# Core.net
KiCad netlist of a schematic drawn in Altium Designer
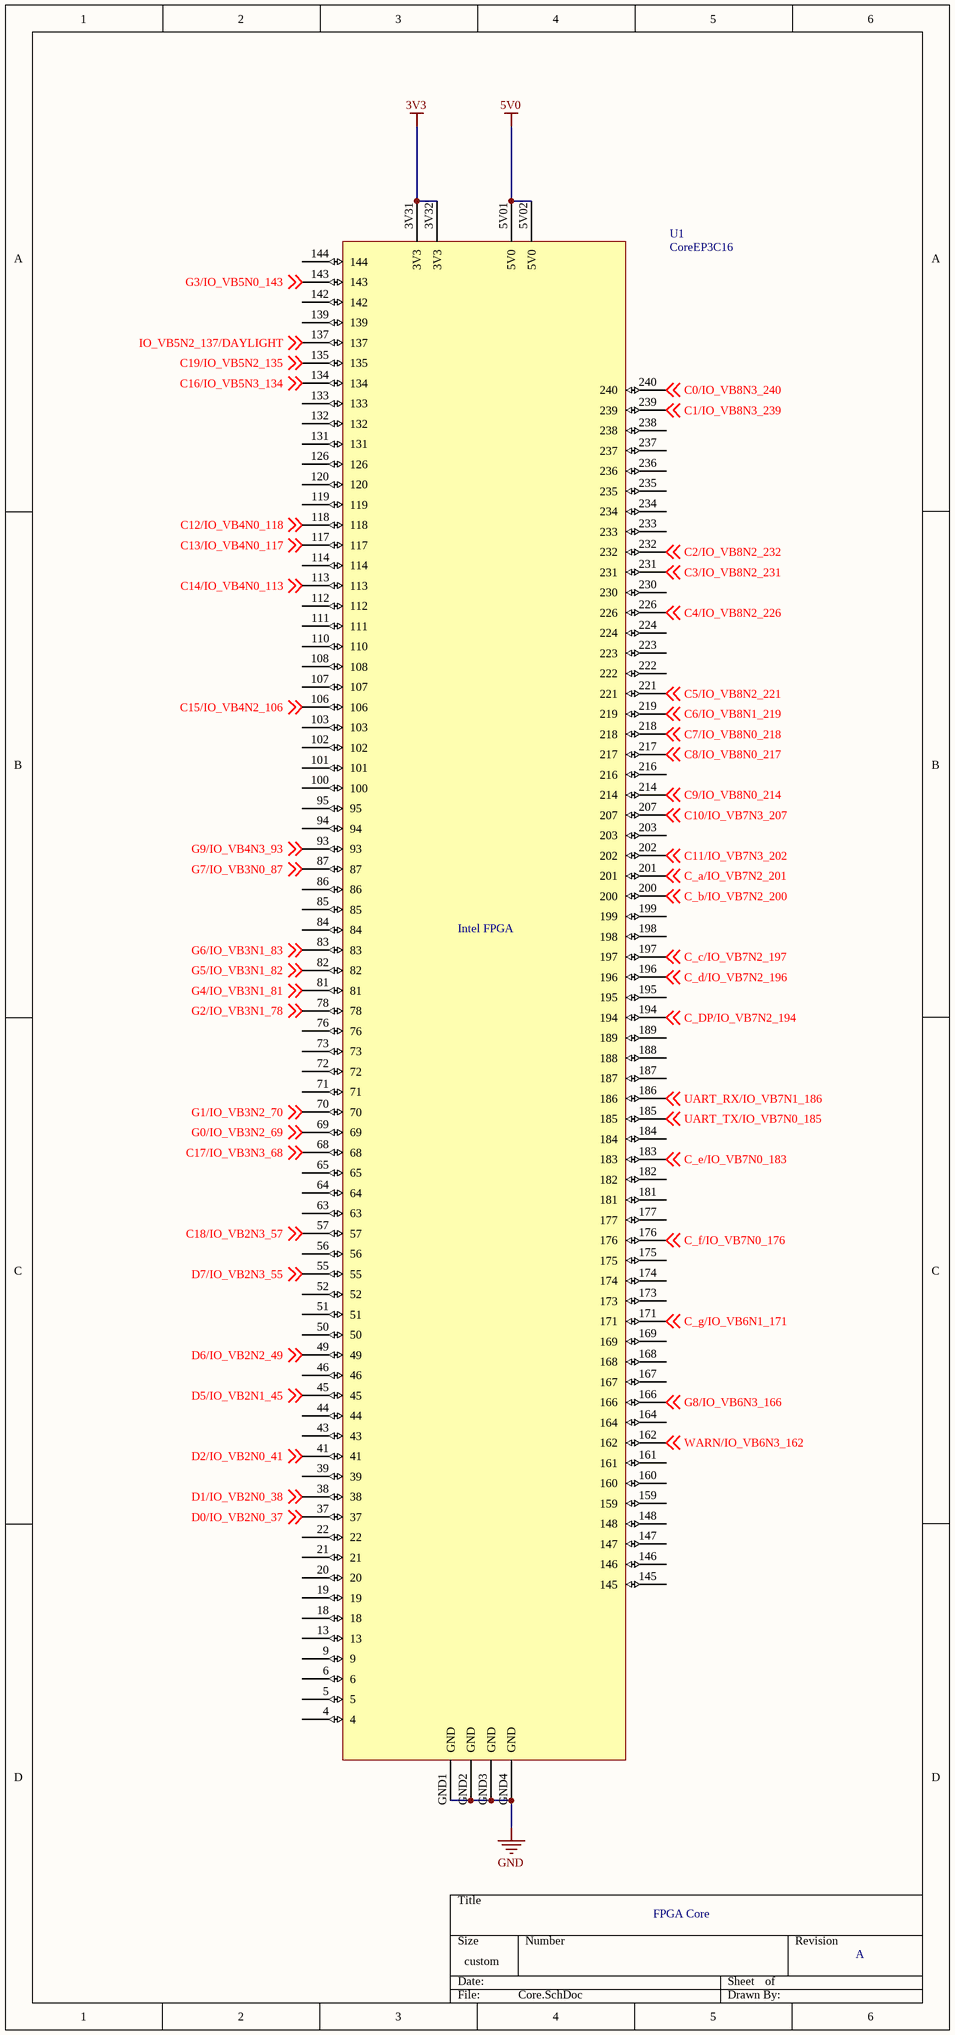
[diagram p0: Core.SchDoc]

(export (version "E")
  (design (tool "Eeschema 10.0.6"))
  (components
    (comp (ref "U1")
      (value "CoreEP3C16")
      (footprint "COREEP3C16")
      (description "Intel FPGA Core")
      (libsource (lib "schematics") (part "CoreEP3C16"))
    )
  )
  (nets
    (net (code "1") (name "3V3") (class "Default")
      (node (ref "U1") (pin "3V31") (pinfunction "3V3_3V31") (pintype "power_in"))
      (node (ref "U1") (pin "3V32") (pinfunction "3V3_3V32") (pintype "power_in"))
    )
    (net (code "2") (name "5V0") (class "Default")
      (node (ref "U1") (pin "5V01") (pinfunction "5V0_5V01") (pintype "power_in"))
      (node (ref "U1") (pin "5V02") (pinfunction "5V0_5V02") (pintype "power_in"))
    )
    (net (code "3") (name "C0{slash}IO_VB8N3_240") (class "Default")
      (node (ref "U1") (pin "240") (pinfunction "240_240") (pintype "bidirectional"))
    )
    (net (code "4") (name "C1{slash}IO_VB8N3_239") (class "Default")
      (node (ref "U1") (pin "239") (pinfunction "239_239") (pintype "bidirectional"))
    )
    (net (code "5") (name "C2{slash}IO_VB8N2_232") (class "Default")
      (node (ref "U1") (pin "232") (pinfunction "232_232") (pintype "bidirectional"))
    )
    (net (code "6") (name "C3{slash}IO_VB8N2_231") (class "Default")
      (node (ref "U1") (pin "231") (pinfunction "231_231") (pintype "bidirectional"))
    )
    (net (code "7") (name "C4{slash}IO_VB8N2_226") (class "Default")
      (node (ref "U1") (pin "226") (pinfunction "226_226") (pintype "bidirectional"))
    )
    (net (code "8") (name "C5{slash}IO_VB8N2_221") (class "Default")
      (node (ref "U1") (pin "221") (pinfunction "221_221") (pintype "bidirectional"))
    )
    (net (code "9") (name "C6{slash}IO_VB8N1_219") (class "Default")
      (node (ref "U1") (pin "219") (pinfunction "219_219") (pintype "bidirectional"))
    )
    (net (code "10") (name "C7{slash}IO_VB8N0_218") (class "Default")
      (node (ref "U1") (pin "218") (pinfunction "218_218") (pintype "bidirectional"))
    )
    (net (code "11") (name "C8{slash}IO_VB8N0_217") (class "Default")
      (node (ref "U1") (pin "217") (pinfunction "217_217") (pintype "bidirectional"))
    )
    (net (code "12") (name "C9{slash}IO_VB8N0_214") (class "Default")
      (node (ref "U1") (pin "214") (pinfunction "214_214") (pintype "bidirectional"))
    )
    (net (code "13") (name "C10{slash}IO_VB7N3_207") (class "Default")
      (node (ref "U1") (pin "207") (pinfunction "207_207") (pintype "bidirectional"))
    )
    (net (code "14") (name "C11{slash}IO_VB7N3_202") (class "Default")
      (node (ref "U1") (pin "202") (pinfunction "202_202") (pintype "bidirectional"))
    )
    (net (code "15") (name "C12{slash}IO_VB4N0_118") (class "Default")
      (node (ref "U1") (pin "118") (pinfunction "118_118") (pintype "bidirectional"))
    )
    (net (code "16") (name "C13{slash}IO_VB4N0_117") (class "Default")
      (node (ref "U1") (pin "117") (pinfunction "117_117") (pintype "bidirectional"))
    )
    (net (code "17") (name "C14{slash}IO_VB4N0_113") (class "Default")
      (node (ref "U1") (pin "113") (pinfunction "113_113") (pintype "bidirectional"))
    )
    (net (code "18") (name "C15{slash}IO_VB4N2_106") (class "Default")
      (node (ref "U1") (pin "106") (pinfunction "106_106") (pintype "bidirectional"))
    )
    (net (code "19") (name "C16{slash}IO_VB5N3_134") (class "Default")
      (node (ref "U1") (pin "134") (pinfunction "134_134") (pintype "bidirectional"))
    )
    (net (code "20") (name "C17{slash}IO_VB3N3_68") (class "Default")
      (node (ref "U1") (pin "68") (pinfunction "68_68") (pintype "bidirectional"))
    )
    (net (code "21") (name "C18{slash}IO_VB2N3_57") (class "Default")
      (node (ref "U1") (pin "57") (pinfunction "57_57") (pintype "bidirectional"))
    )
    (net (code "22") (name "C19{slash}IO_VB5N2_135") (class "Default")
      (node (ref "U1") (pin "135") (pinfunction "135_135") (pintype "bidirectional"))
    )
    (net (code "23") (name "C_DP{slash}IO_VB7N2_194") (class "Default")
      (node (ref "U1") (pin "194") (pinfunction "194_194") (pintype "bidirectional"))
    )
    (net (code "24") (name "C_a{slash}IO_VB7N2_201") (class "Default")
      (node (ref "U1") (pin "201") (pinfunction "201_201") (pintype "bidirectional"))
    )
    (net (code "25") (name "C_b{slash}IO_VB7N2_200") (class "Default")
      (node (ref "U1") (pin "200") (pinfunction "200_200") (pintype "bidirectional"))
    )
    (net (code "26") (name "C_c{slash}IO_VB7N2_197") (class "Default")
      (node (ref "U1") (pin "197") (pinfunction "197_197") (pintype "bidirectional"))
    )
    (net (code "27") (name "C_d{slash}IO_VB7N2_196") (class "Default")
      (node (ref "U1") (pin "196") (pinfunction "196_196") (pintype "bidirectional"))
    )
    (net (code "28") (name "C_e{slash}IO_VB7N0_183") (class "Default")
      (node (ref "U1") (pin "183") (pinfunction "183_183") (pintype "bidirectional"))
    )
    (net (code "29") (name "C_f{slash}IO_VB7N0_176") (class "Default")
      (node (ref "U1") (pin "176") (pinfunction "176_176") (pintype "bidirectional"))
    )
    (net (code "30") (name "C_g{slash}IO_VB6N1_171") (class "Default")
      (node (ref "U1") (pin "171") (pinfunction "171_171") (pintype "bidirectional"))
    )
    (net (code "31") (name "D0{slash}IO_VB2N0_37") (class "Default")
      (node (ref "U1") (pin "37") (pinfunction "37_37") (pintype "bidirectional"))
    )
    (net (code "32") (name "D1{slash}IO_VB2N0_38") (class "Default")
      (node (ref "U1") (pin "38") (pinfunction "38_38") (pintype "bidirectional"))
    )
    (net (code "33") (name "D2{slash}IO_VB2N0_41") (class "Default")
      (node (ref "U1") (pin "41") (pinfunction "41_41") (pintype "bidirectional"))
    )
    (net (code "34") (name "D5{slash}IO_VB2N1_45") (class "Default")
      (node (ref "U1") (pin "45") (pinfunction "45_45") (pintype "bidirectional"))
    )
    (net (code "35") (name "D6{slash}IO_VB2N2_49") (class "Default")
      (node (ref "U1") (pin "49") (pinfunction "49_49") (pintype "bidirectional"))
    )
    (net (code "36") (name "D7{slash}IO_VB2N3_55") (class "Default")
      (node (ref "U1") (pin "55") (pinfunction "55_55") (pintype "bidirectional"))
    )
    (net (code "37") (name "G0{slash}IO_VB3N2_69") (class "Default")
      (node (ref "U1") (pin "69") (pinfunction "69_69") (pintype "bidirectional"))
    )
    (net (code "38") (name "G1{slash}IO_VB3N2_70") (class "Default")
      (node (ref "U1") (pin "70") (pinfunction "70_70") (pintype "bidirectional"))
    )
    (net (code "39") (name "G2{slash}IO_VB3N1_78") (class "Default")
      (node (ref "U1") (pin "78") (pinfunction "78_78") (pintype "bidirectional"))
    )
    (net (code "40") (name "G3{slash}IO_VB5N0_143") (class "Default")
      (node (ref "U1") (pin "143") (pinfunction "143_143") (pintype "bidirectional"))
    )
    (net (code "41") (name "G4{slash}IO_VB3N1_81") (class "Default")
      (node (ref "U1") (pin "81") (pinfunction "81_81") (pintype "bidirectional"))
    )
    (net (code "42") (name "G5{slash}IO_VB3N1_82") (class "Default")
      (node (ref "U1") (pin "82") (pinfunction "82_82") (pintype "bidirectional"))
    )
    (net (code "43") (name "G6{slash}IO_VB3N1_83") (class "Default")
      (node (ref "U1") (pin "83") (pinfunction "83_83") (pintype "bidirectional"))
    )
    (net (code "44") (name "G7{slash}IO_VB3N0_87") (class "Default")
      (node (ref "U1") (pin "87") (pinfunction "87_87") (pintype "bidirectional"))
    )
    (net (code "45") (name "G8{slash}IO_VB6N3_166") (class "Default")
      (node (ref "U1") (pin "166") (pinfunction "166_166") (pintype "bidirectional"))
    )
    (net (code "46") (name "G9{slash}IO_VB4N3_93") (class "Default")
      (node (ref "U1") (pin "93") (pinfunction "93_93") (pintype "bidirectional"))
    )
    (net (code "47") (name "GND") (class "Default")
      (node (ref "U1") (pin "GND1") (pinfunction "GND_GND1") (pintype "power_in"))
      (node (ref "U1") (pin "GND2") (pinfunction "GND_GND2") (pintype "power_in"))
      (node (ref "U1") (pin "GND3") (pinfunction "GND_GND3") (pintype "power_in"))
      (node (ref "U1") (pin "GND4") (pinfunction "GND_GND4") (pintype "power_in"))
    )
    (net (code "48") (name "IO_VB5N2_137{slash}DAYLIGHT") (class "Default")
      (node (ref "U1") (pin "137") (pinfunction "137_137") (pintype "bidirectional"))
    )
    (net (code "49") (name "UART_RX{slash}IO_VB7N1_186") (class "Default")
      (node (ref "U1") (pin "186") (pinfunction "186_186") (pintype "bidirectional"))
    )
    (net (code "50") (name "UART_TX{slash}IO_VB7N0_185") (class "Default")
      (node (ref "U1") (pin "185") (pinfunction "185_185") (pintype "bidirectional"))
    )
    (net (code "51") (name "WARN{slash}IO_VB6N3_162") (class "Default")
      (node (ref "U1") (pin "162") (pinfunction "162_162") (pintype "bidirectional"))
    )
    (net (code "52") (name "unconnected-(U1-Pad4)") (class "Default")
      (node (ref "U1") (pin "4") (pinfunction "4_4") (pintype "bidirectional"))
    )
    (net (code "53") (name "unconnected-(U1-Pad5)") (class "Default")
      (node (ref "U1") (pin "5") (pinfunction "5_5") (pintype "bidirectional"))
    )
    (net (code "54") (name "unconnected-(U1-Pad6)") (class "Default")
      (node (ref "U1") (pin "6") (pinfunction "6_6") (pintype "bidirectional"))
    )
    (net (code "55") (name "unconnected-(U1-Pad9)") (class "Default")
      (node (ref "U1") (pin "9") (pinfunction "9_9") (pintype "bidirectional"))
    )
    (net (code "56") (name "unconnected-(U1-Pad13)") (class "Default")
      (node (ref "U1") (pin "13") (pinfunction "13_13") (pintype "bidirectional"))
    )
    (net (code "57") (name "unconnected-(U1-Pad18)") (class "Default")
      (node (ref "U1") (pin "18") (pinfunction "18_18") (pintype "bidirectional"))
    )
    (net (code "58") (name "unconnected-(U1-Pad19)") (class "Default")
      (node (ref "U1") (pin "19") (pinfunction "19_19") (pintype "bidirectional"))
    )
    (net (code "59") (name "unconnected-(U1-Pad20)") (class "Default")
      (node (ref "U1") (pin "20") (pinfunction "20_20") (pintype "bidirectional"))
    )
    (net (code "60") (name "unconnected-(U1-Pad21)") (class "Default")
      (node (ref "U1") (pin "21") (pinfunction "21_21") (pintype "bidirectional"))
    )
    (net (code "61") (name "unconnected-(U1-Pad22)") (class "Default")
      (node (ref "U1") (pin "22") (pinfunction "22_22") (pintype "bidirectional"))
    )
    (net (code "62") (name "unconnected-(U1-Pad39)") (class "Default")
      (node (ref "U1") (pin "39") (pinfunction "39_39") (pintype "bidirectional"))
    )
    (net (code "63") (name "unconnected-(U1-Pad43)") (class "Default")
      (node (ref "U1") (pin "43") (pinfunction "43_43") (pintype "bidirectional"))
    )
    (net (code "64") (name "unconnected-(U1-Pad44)") (class "Default")
      (node (ref "U1") (pin "44") (pinfunction "44_44") (pintype "bidirectional"))
    )
    (net (code "65") (name "unconnected-(U1-Pad46)") (class "Default")
      (node (ref "U1") (pin "46") (pinfunction "46_46") (pintype "bidirectional"))
    )
    (net (code "66") (name "unconnected-(U1-Pad50)") (class "Default")
      (node (ref "U1") (pin "50") (pinfunction "50_50") (pintype "bidirectional"))
    )
    (net (code "67") (name "unconnected-(U1-Pad51)") (class "Default")
      (node (ref "U1") (pin "51") (pinfunction "51_51") (pintype "bidirectional"))
    )
    (net (code "68") (name "unconnected-(U1-Pad52)") (class "Default")
      (node (ref "U1") (pin "52") (pinfunction "52_52") (pintype "bidirectional"))
    )
    (net (code "69") (name "unconnected-(U1-Pad56)") (class "Default")
      (node (ref "U1") (pin "56") (pinfunction "56_56") (pintype "bidirectional"))
    )
    (net (code "70") (name "unconnected-(U1-Pad63)") (class "Default")
      (node (ref "U1") (pin "63") (pinfunction "63_63") (pintype "bidirectional"))
    )
    (net (code "71") (name "unconnected-(U1-Pad64)") (class "Default")
      (node (ref "U1") (pin "64") (pinfunction "64_64") (pintype "bidirectional"))
    )
    (net (code "72") (name "unconnected-(U1-Pad65)") (class "Default")
      (node (ref "U1") (pin "65") (pinfunction "65_65") (pintype "bidirectional"))
    )
    (net (code "73") (name "unconnected-(U1-Pad71)") (class "Default")
      (node (ref "U1") (pin "71") (pinfunction "71_71") (pintype "bidirectional"))
    )
    (net (code "74") (name "unconnected-(U1-Pad72)") (class "Default")
      (node (ref "U1") (pin "72") (pinfunction "72_72") (pintype "bidirectional"))
    )
    (net (code "75") (name "unconnected-(U1-Pad73)") (class "Default")
      (node (ref "U1") (pin "73") (pinfunction "73_73") (pintype "bidirectional"))
    )
    (net (code "76") (name "unconnected-(U1-Pad76)") (class "Default")
      (node (ref "U1") (pin "76") (pinfunction "76_76") (pintype "bidirectional"))
    )
    (net (code "77") (name "unconnected-(U1-Pad84)") (class "Default")
      (node (ref "U1") (pin "84") (pinfunction "84_84") (pintype "bidirectional"))
    )
    (net (code "78") (name "unconnected-(U1-Pad85)") (class "Default")
      (node (ref "U1") (pin "85") (pinfunction "85_85") (pintype "bidirectional"))
    )
    (net (code "79") (name "unconnected-(U1-Pad86)") (class "Default")
      (node (ref "U1") (pin "86") (pinfunction "86_86") (pintype "bidirectional"))
    )
    (net (code "80") (name "unconnected-(U1-Pad94)") (class "Default")
      (node (ref "U1") (pin "94") (pinfunction "94_94") (pintype "bidirectional"))
    )
    (net (code "81") (name "unconnected-(U1-Pad95)") (class "Default")
      (node (ref "U1") (pin "95") (pinfunction "95_95") (pintype "bidirectional"))
    )
    (net (code "82") (name "unconnected-(U1-Pad100)") (class "Default")
      (node (ref "U1") (pin "100") (pinfunction "100_100") (pintype "bidirectional"))
    )
    (net (code "83") (name "unconnected-(U1-Pad101)") (class "Default")
      (node (ref "U1") (pin "101") (pinfunction "101_101") (pintype "bidirectional"))
    )
    (net (code "84") (name "unconnected-(U1-Pad102)") (class "Default")
      (node (ref "U1") (pin "102") (pinfunction "102_102") (pintype "bidirectional"))
    )
    (net (code "85") (name "unconnected-(U1-Pad103)") (class "Default")
      (node (ref "U1") (pin "103") (pinfunction "103_103") (pintype "bidirectional"))
    )
    (net (code "86") (name "unconnected-(U1-Pad107)") (class "Default")
      (node (ref "U1") (pin "107") (pinfunction "107_107") (pintype "bidirectional"))
    )
    (net (code "87") (name "unconnected-(U1-Pad108)") (class "Default")
      (node (ref "U1") (pin "108") (pinfunction "108_108") (pintype "bidirectional"))
    )
    (net (code "88") (name "unconnected-(U1-Pad110)") (class "Default")
      (node (ref "U1") (pin "110") (pinfunction "110_110") (pintype "bidirectional"))
    )
    (net (code "89") (name "unconnected-(U1-Pad111)") (class "Default")
      (node (ref "U1") (pin "111") (pinfunction "111_111") (pintype "bidirectional"))
    )
    (net (code "90") (name "unconnected-(U1-Pad112)") (class "Default")
      (node (ref "U1") (pin "112") (pinfunction "112_112") (pintype "bidirectional"))
    )
    (net (code "91") (name "unconnected-(U1-Pad114)") (class "Default")
      (node (ref "U1") (pin "114") (pinfunction "114_114") (pintype "bidirectional"))
    )
    (net (code "92") (name "unconnected-(U1-Pad119)") (class "Default")
      (node (ref "U1") (pin "119") (pinfunction "119_119") (pintype "bidirectional"))
    )
    (net (code "93") (name "unconnected-(U1-Pad120)") (class "Default")
      (node (ref "U1") (pin "120") (pinfunction "120_120") (pintype "bidirectional"))
    )
    (net (code "94") (name "unconnected-(U1-Pad126)") (class "Default")
      (node (ref "U1") (pin "126") (pinfunction "126_126") (pintype "bidirectional"))
    )
    (net (code "95") (name "unconnected-(U1-Pad131)") (class "Default")
      (node (ref "U1") (pin "131") (pinfunction "131_131") (pintype "bidirectional"))
    )
    (net (code "96") (name "unconnected-(U1-Pad132)") (class "Default")
      (node (ref "U1") (pin "132") (pinfunction "132_132") (pintype "bidirectional"))
    )
    (net (code "97") (name "unconnected-(U1-Pad133)") (class "Default")
      (node (ref "U1") (pin "133") (pinfunction "133_133") (pintype "bidirectional"))
    )
    (net (code "98") (name "unconnected-(U1-Pad139)") (class "Default")
      (node (ref "U1") (pin "139") (pinfunction "139_139") (pintype "bidirectional"))
    )
    (net (code "99") (name "unconnected-(U1-Pad142)") (class "Default")
      (node (ref "U1") (pin "142") (pinfunction "142_142") (pintype "bidirectional"))
    )
    (net (code "100") (name "unconnected-(U1-Pad144)") (class "Default")
      (node (ref "U1") (pin "144") (pinfunction "144_144") (pintype "bidirectional"))
    )
    (net (code "101") (name "unconnected-(U1-Pad145)") (class "Default")
      (node (ref "U1") (pin "145") (pinfunction "145_145") (pintype "bidirectional"))
    )
    (net (code "102") (name "unconnected-(U1-Pad146)") (class "Default")
      (node (ref "U1") (pin "146") (pinfunction "146_146") (pintype "bidirectional"))
    )
    (net (code "103") (name "unconnected-(U1-Pad147)") (class "Default")
      (node (ref "U1") (pin "147") (pinfunction "147_147") (pintype "bidirectional"))
    )
    (net (code "104") (name "unconnected-(U1-Pad148)") (class "Default")
      (node (ref "U1") (pin "148") (pinfunction "148_148") (pintype "bidirectional"))
    )
    (net (code "105") (name "unconnected-(U1-Pad159)") (class "Default")
      (node (ref "U1") (pin "159") (pinfunction "159_159") (pintype "bidirectional"))
    )
    (net (code "106") (name "unconnected-(U1-Pad160)") (class "Default")
      (node (ref "U1") (pin "160") (pinfunction "160_160") (pintype "bidirectional"))
    )
    (net (code "107") (name "unconnected-(U1-Pad161)") (class "Default")
      (node (ref "U1") (pin "161") (pinfunction "161_161") (pintype "bidirectional"))
    )
    (net (code "108") (name "unconnected-(U1-Pad164)") (class "Default")
      (node (ref "U1") (pin "164") (pinfunction "164_164") (pintype "bidirectional"))
    )
    (net (code "109") (name "unconnected-(U1-Pad167)") (class "Default")
      (node (ref "U1") (pin "167") (pinfunction "167_167") (pintype "bidirectional"))
    )
    (net (code "110") (name "unconnected-(U1-Pad168)") (class "Default")
      (node (ref "U1") (pin "168") (pinfunction "168_168") (pintype "bidirectional"))
    )
    (net (code "111") (name "unconnected-(U1-Pad169)") (class "Default")
      (node (ref "U1") (pin "169") (pinfunction "169_169") (pintype "bidirectional"))
    )
    (net (code "112") (name "unconnected-(U1-Pad173)") (class "Default")
      (node (ref "U1") (pin "173") (pinfunction "173_173") (pintype "bidirectional"))
    )
    (net (code "113") (name "unconnected-(U1-Pad174)") (class "Default")
      (node (ref "U1") (pin "174") (pinfunction "174_174") (pintype "bidirectional"))
    )
    (net (code "114") (name "unconnected-(U1-Pad175)") (class "Default")
      (node (ref "U1") (pin "175") (pinfunction "175_175") (pintype "bidirectional"))
    )
    (net (code "115") (name "unconnected-(U1-Pad177)") (class "Default")
      (node (ref "U1") (pin "177") (pinfunction "177_177") (pintype "bidirectional"))
    )
    (net (code "116") (name "unconnected-(U1-Pad181)") (class "Default")
      (node (ref "U1") (pin "181") (pinfunction "181_181") (pintype "bidirectional"))
    )
    (net (code "117") (name "unconnected-(U1-Pad182)") (class "Default")
      (node (ref "U1") (pin "182") (pinfunction "182_182") (pintype "bidirectional"))
    )
    (net (code "118") (name "unconnected-(U1-Pad184)") (class "Default")
      (node (ref "U1") (pin "184") (pinfunction "184_184") (pintype "bidirectional"))
    )
    (net (code "119") (name "unconnected-(U1-Pad187)") (class "Default")
      (node (ref "U1") (pin "187") (pinfunction "187_187") (pintype "bidirectional"))
    )
    (net (code "120") (name "unconnected-(U1-Pad188)") (class "Default")
      (node (ref "U1") (pin "188") (pinfunction "188_188") (pintype "bidirectional"))
    )
    (net (code "121") (name "unconnected-(U1-Pad189)") (class "Default")
      (node (ref "U1") (pin "189") (pinfunction "189_189") (pintype "bidirectional"))
    )
    (net (code "122") (name "unconnected-(U1-Pad195)") (class "Default")
      (node (ref "U1") (pin "195") (pinfunction "195_195") (pintype "bidirectional"))
    )
    (net (code "123") (name "unconnected-(U1-Pad198)") (class "Default")
      (node (ref "U1") (pin "198") (pinfunction "198_198") (pintype "bidirectional"))
    )
    (net (code "124") (name "unconnected-(U1-Pad199)") (class "Default")
      (node (ref "U1") (pin "199") (pinfunction "199_199") (pintype "bidirectional"))
    )
    (net (code "125") (name "unconnected-(U1-Pad203)") (class "Default")
      (node (ref "U1") (pin "203") (pinfunction "203_203") (pintype "bidirectional"))
    )
    (net (code "126") (name "unconnected-(U1-Pad216)") (class "Default")
      (node (ref "U1") (pin "216") (pinfunction "216_216") (pintype "bidirectional"))
    )
    (net (code "127") (name "unconnected-(U1-Pad222)") (class "Default")
      (node (ref "U1") (pin "222") (pinfunction "222_222") (pintype "bidirectional"))
    )
    (net (code "128") (name "unconnected-(U1-Pad223)") (class "Default")
      (node (ref "U1") (pin "223") (pinfunction "223_223") (pintype "bidirectional"))
    )
    (net (code "129") (name "unconnected-(U1-Pad224)") (class "Default")
      (node (ref "U1") (pin "224") (pinfunction "224_224") (pintype "bidirectional"))
    )
    (net (code "130") (name "unconnected-(U1-Pad230)") (class "Default")
      (node (ref "U1") (pin "230") (pinfunction "230_230") (pintype "bidirectional"))
    )
    (net (code "131") (name "unconnected-(U1-Pad233)") (class "Default")
      (node (ref "U1") (pin "233") (pinfunction "233_233") (pintype "bidirectional"))
    )
    (net (code "132") (name "unconnected-(U1-Pad234)") (class "Default")
      (node (ref "U1") (pin "234") (pinfunction "234_234") (pintype "bidirectional"))
    )
    (net (code "133") (name "unconnected-(U1-Pad235)") (class "Default")
      (node (ref "U1") (pin "235") (pinfunction "235_235") (pintype "bidirectional"))
    )
    (net (code "134") (name "unconnected-(U1-Pad236)") (class "Default")
      (node (ref "U1") (pin "236") (pinfunction "236_236") (pintype "bidirectional"))
    )
    (net (code "135") (name "unconnected-(U1-Pad237)") (class "Default")
      (node (ref "U1") (pin "237") (pinfunction "237_237") (pintype "bidirectional"))
    )
    (net (code "136") (name "unconnected-(U1-Pad238)") (class "Default")
      (node (ref "U1") (pin "238") (pinfunction "238_238") (pintype "bidirectional"))
    )
  )
)
